# control_03_12_2018.net
KiCad netlist of a schematic drawn in EAGLE
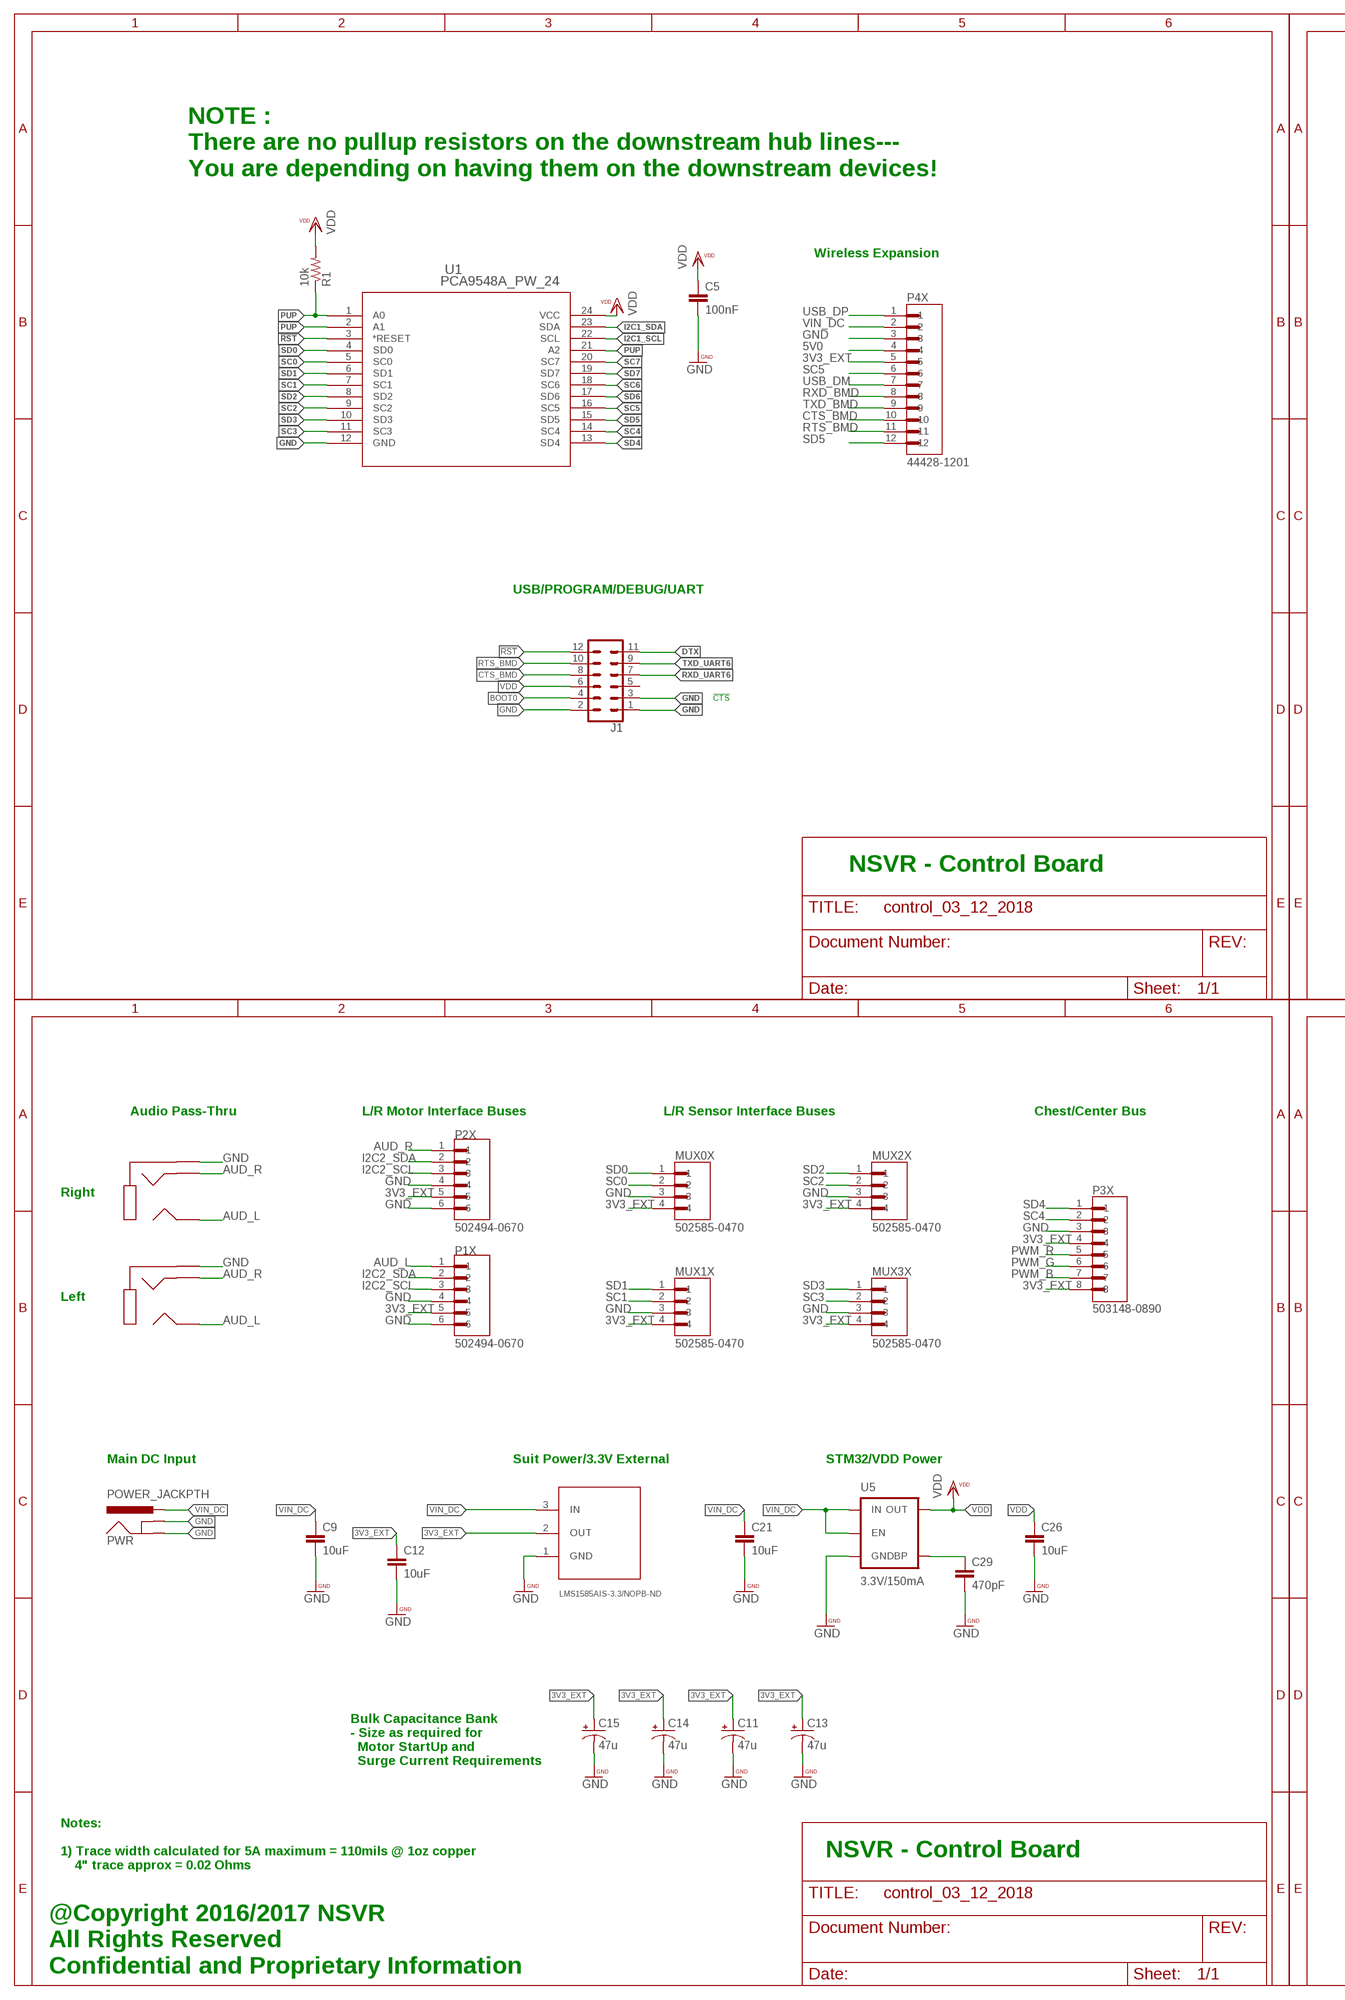
[diagram p0: schematic, sheet 1, part 1 of 2]
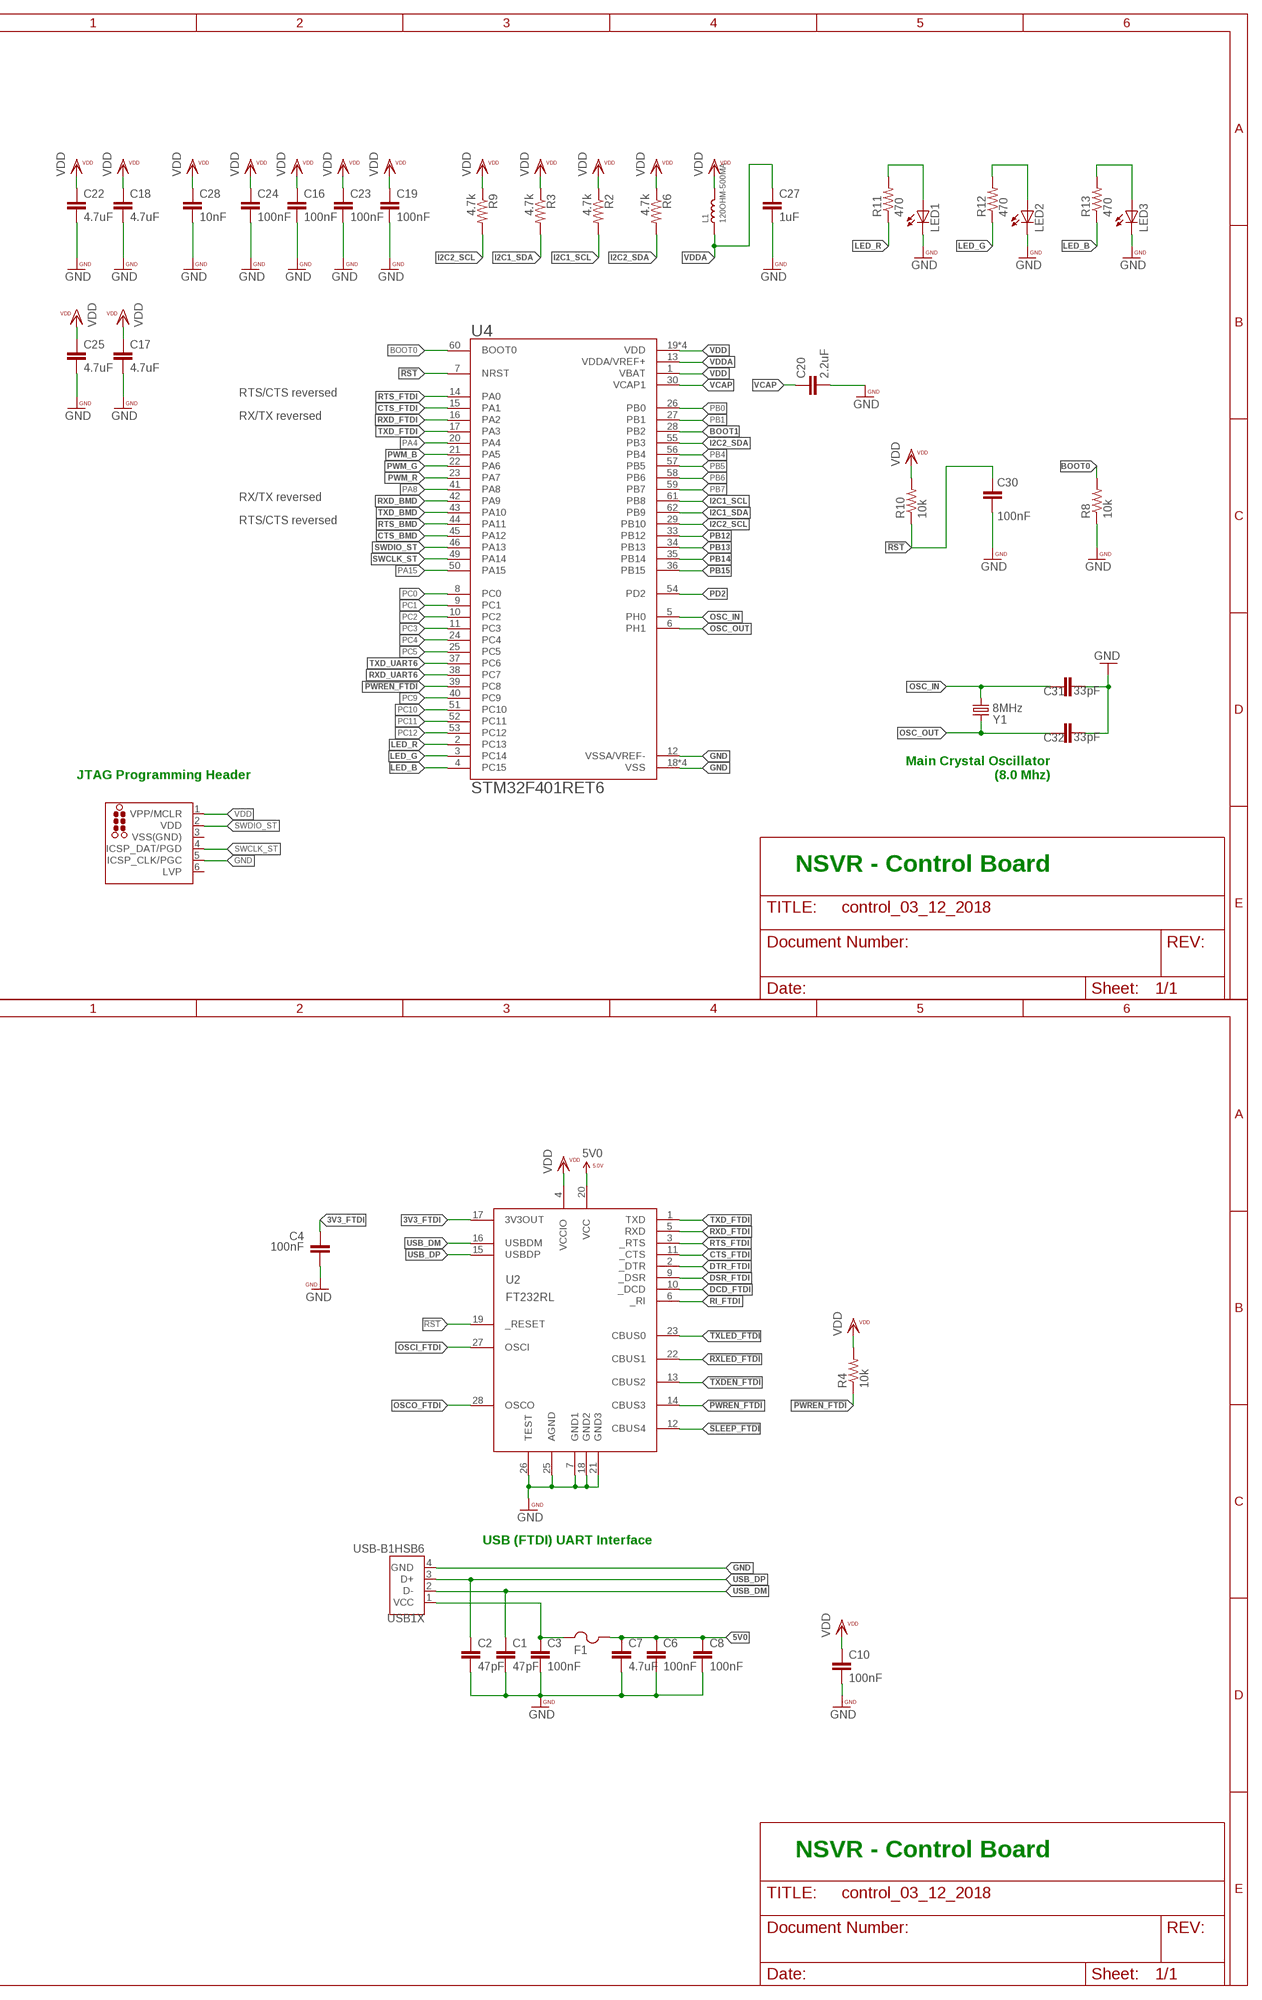
[diagram p1: schematic, sheet 1, part 2 of 2]

(export (version "E")
  (design (tool "Eeschema 10.0.6"))
  (components
    (comp (ref "C1")
      (value "47pF")
      (footprint "eagle-import:0402-CAP")
      (libsource (lib "eagle-import") (part "CAP0402-CAP"))
    )
    (comp (ref "C2")
      (value "47pF")
      (footprint "eagle-import:0402-CAP")
      (libsource (lib "eagle-import") (part "CAP0402-CAP"))
    )
    (comp (ref "C3")
      (value "100nF")
      (footprint "eagle-import:0402-CAP")
      (libsource (lib "eagle-import") (part "CAP0402-CAP"))
    )
    (comp (ref "C4")
      (value "100nF")
      (footprint "eagle-import:0402-CAP")
      (libsource (lib "eagle-import") (part "CAP0402-CAP"))
    )
    (comp (ref "C5")
      (value "100nF")
      (footprint "eagle-import:0402-CAP")
      (libsource (lib "eagle-import") (part "CAP0402-CAP"))
    )
    (comp (ref "C6")
      (value "100nF")
      (footprint "eagle-import:0402-CAP")
      (libsource (lib "eagle-import") (part "CAP0402-CAP"))
    )
    (comp (ref "C7")
      (value "4.7uF")
      (footprint "eagle-import:0402-CAP")
      (libsource (lib "eagle-import") (part "CAP0402-CAP"))
    )
    (comp (ref "C8")
      (value "100nF")
      (footprint "eagle-import:0402-CAP")
      (libsource (lib "eagle-import") (part "CAP0402-CAP"))
    )
    (comp (ref "C9")
      (value "10uF")
      (footprint "eagle-import:0603-CAP")
      (libsource (lib "eagle-import") (part "CAP0603-CAP"))
    )
    (comp (ref "C10")
      (value "100nF")
      (footprint "eagle-import:0402-CAP")
      (libsource (lib "eagle-import") (part "CAP0402-CAP"))
    )
    (comp (ref "C11")
      (value "47u")
      (footprint "eagle-import:PANASONIC_D")
      (libsource (lib "eagle-import") (part "CAP_POLD"))
    )
    (comp (ref "C12")
      (value "10uF")
      (footprint "eagle-import:0603-CAP")
      (libsource (lib "eagle-import") (part "CAP0603-CAP"))
    )
    (comp (ref "C13")
      (value "47u")
      (footprint "eagle-import:PANASONIC_D")
      (libsource (lib "eagle-import") (part "CAP_POLD"))
    )
    (comp (ref "C14")
      (value "47u")
      (footprint "eagle-import:PANASONIC_D")
      (libsource (lib "eagle-import") (part "CAP_POLD"))
    )
    (comp (ref "C15")
      (value "47u")
      (footprint "eagle-import:PANASONIC_D")
      (libsource (lib "eagle-import") (part "CAP_POLD"))
    )
    (comp (ref "C16")
      (value "100nF")
      (footprint "eagle-import:0402-CAP")
      (libsource (lib "eagle-import") (part "CAP0402-CAP"))
    )
    (comp (ref "C17")
      (value "4.7uF")
      (footprint "eagle-import:0402-CAP")
      (libsource (lib "eagle-import") (part "CAP0402-CAP"))
    )
    (comp (ref "C18")
      (value "4.7uF")
      (footprint "eagle-import:0402-CAP")
      (libsource (lib "eagle-import") (part "CAP0402-CAP"))
    )
    (comp (ref "C19")
      (value "100nF")
      (footprint "eagle-import:0402-CAP")
      (libsource (lib "eagle-import") (part "CAP0402-CAP"))
    )
    (comp (ref "C20")
      (value "2.2uF")
      (footprint "eagle-import:0402-CAP")
      (libsource (lib "eagle-import") (part "CAP0402-CAP"))
    )
    (comp (ref "C21")
      (value "10uF")
      (footprint "eagle-import:0603-CAP")
      (libsource (lib "eagle-import") (part "CAP0603-CAP"))
    )
    (comp (ref "C22")
      (value "4.7uF")
      (footprint "eagle-import:0402-CAP")
      (libsource (lib "eagle-import") (part "CAP0402-CAP"))
    )
    (comp (ref "C23")
      (value "100nF")
      (footprint "eagle-import:0402-CAP")
      (libsource (lib "eagle-import") (part "CAP0402-CAP"))
    )
    (comp (ref "C24")
      (value "100nF")
      (footprint "eagle-import:0402-CAP")
      (libsource (lib "eagle-import") (part "CAP0402-CAP"))
    )
    (comp (ref "C25")
      (value "4.7uF")
      (footprint "eagle-import:0402-CAP")
      (libsource (lib "eagle-import") (part "CAP0402-CAP"))
    )
    (comp (ref "C26")
      (value "10uF")
      (footprint "eagle-import:0603-CAP")
      (libsource (lib "eagle-import") (part "CAP0603-CAP"))
    )
    (comp (ref "C27")
      (value "1uF")
      (footprint "eagle-import:0402-CAP")
      (libsource (lib "eagle-import") (part "CAP0402-CAP"))
    )
    (comp (ref "C28")
      (value "10nF")
      (footprint "eagle-import:0402-CAP")
      (libsource (lib "eagle-import") (part "CAP0402-CAP"))
    )
    (comp (ref "C29")
      (value "470pF")
      (footprint "eagle-import:0402-CAP")
      (libsource (lib "eagle-import") (part "CAP0402-CAP"))
    )
    (comp (ref "C30")
      (value "100nF")
      (footprint "eagle-import:0402-CAP")
      (libsource (lib "eagle-import") (part "CAP0402-CAP"))
    )
    (comp (ref "C31")
      (value "33pF")
      (footprint "eagle-import:0402-CAP")
      (libsource (lib "eagle-import") (part "CAP0402-CAP"))
    )
    (comp (ref "C32")
      (value "33pF")
      (footprint "eagle-import:0402-CAP")
      (libsource (lib "eagle-import") (part "CAP0402-CAP"))
    )
    (comp (ref "F1")
      (value "1206L050YR")
      (footprint "eagle-import:1206LSERIES")
      (fields (field (name "COPYRIGHT") "Copyright C 2015 Accelerated Designs. All rights reserved"))
      (libsource (lib "eagle-import") (part "1206L050YR"))
    )
    (comp (ref "J1")
      (value "CONN_06X2SMD_FEMALE")
      (footprint "eagle-import:2X6_SMD")
      (libsource (lib "eagle-import") (part "CONN_06X2SMD_FEMALE"))
    )
    (comp (ref "J_ST")
      (value "TC2030-MCP-NL")
      (footprint "eagle-import:TC2030-MCP-NL")
      (libsource (lib "eagle-import") (part "TC2030-MCP-NL"))
    )
    (comp (ref "L1")
      (value "120OHM-500MA")
      (footprint "eagle-import:L0603")
      (fields (field (name "MPN") "BLM18AG121SN1D"))
      (libsource (lib "eagle-import") (part "SMD-FERRITE-CHIP-120-OHM-500MA(0603)"))
    )
    (comp (ref "LED1")
      (value "LEDCHIP-LED0603")
      (footprint "eagle-import:CHIP-LED0603")
      (libsource (lib "eagle-import") (part "LEDCHIP-LED0603"))
    )
    (comp (ref "LED2")
      (value "LEDCHIP-LED0603")
      (footprint "eagle-import:CHIP-LED0603")
      (libsource (lib "eagle-import") (part "LEDCHIP-LED0603"))
    )
    (comp (ref "LED3")
      (value "LEDCHIP-LED0603")
      (footprint "eagle-import:CHIP-LED0603")
      (libsource (lib "eagle-import") (part "LEDCHIP-LED0603"))
    )
    (comp (ref "MUX0X")
      (value "502585-0470")
      (footprint "eagle-import:MOLEX_502585-0470")
      (fields (field (name "MF") "Molex"))
      (libsource (lib "eagle-import") (part "502585-0470"))
    )
    (comp (ref "MUX1X")
      (value "502585-0470")
      (footprint "eagle-import:MOLEX_502585-0470")
      (fields (field (name "MF") "Molex"))
      (libsource (lib "eagle-import") (part "502585-0470"))
    )
    (comp (ref "MUX2X")
      (value "502585-0470")
      (footprint "eagle-import:MOLEX_502585-0470")
      (fields (field (name "MF") "Molex"))
      (libsource (lib "eagle-import") (part "502585-0470"))
    )
    (comp (ref "MUX3X")
      (value "502585-0470")
      (footprint "eagle-import:MOLEX_502585-0470")
      (fields (field (name "MF") "Molex"))
      (libsource (lib "eagle-import") (part "502585-0470"))
    )
    (comp (ref "P1X")
      (value "502494-0670")
      (footprint "eagle-import:MOLEX_502494-0670")
      (fields (field (name "MF") "Molex"))
      (libsource (lib "eagle-import") (part "502494-0670"))
    )
    (comp (ref "P2X")
      (value "502494-0670")
      (footprint "eagle-import:MOLEX_502494-0670")
      (fields (field (name "MF") "Molex"))
      (libsource (lib "eagle-import") (part "502494-0670"))
    )
    (comp (ref "P3X")
      (value "503148-0890")
      (footprint "eagle-import:MOLEX_503148-0890")
      (fields (field (name "MF") "Molex"))
      (libsource (lib "eagle-import") (part "503148-0890"))
    )
    (comp (ref "P4X")
      (value "44428-1201")
      (footprint "eagle-import:MOLEX_44428-1201")
      (fields (field (name "MF") "Molex"))
      (libsource (lib "eagle-import") (part "44428-1201"))
    )
    (comp (ref "PJ1")
      (value "SJ1-3513N")
      (footprint "eagle-import:SJ1-351XN")
      (libsource (lib "eagle-import") (part "SJ1-3513N"))
    )
    (comp (ref "PJ2")
      (value "SJ1-3513N")
      (footprint "eagle-import:SJ1-351XN")
      (libsource (lib "eagle-import") (part "SJ1-3513N"))
    )
    (comp (ref "PWR")
      (value "POWER_JACKPTH")
      (footprint "eagle-import:POWER_JACK_PTH")
      (libsource (lib "eagle-import") (part "POWER_JACKPTH"))
    )
    (comp (ref "R1")
      (value "10k")
      (footprint "eagle-import:EIA-0402")
      (libsource (lib "eagle-import") (part "RESISTOR0402-TYP"))
    )
    (comp (ref "R2")
      (value "4.7k")
      (footprint "eagle-import:EIA-0402")
      (libsource (lib "eagle-import") (part "RESISTOR0402-TYP"))
    )
    (comp (ref "R3")
      (value "4.7k")
      (footprint "eagle-import:EIA-0402")
      (libsource (lib "eagle-import") (part "RESISTOR0402-TYP"))
    )
    (comp (ref "R4")
      (value "10k")
      (footprint "eagle-import:EIA-0402")
      (libsource (lib "eagle-import") (part "RESISTOR0402-TYP"))
    )
    (comp (ref "R6")
      (value "4.7k")
      (footprint "eagle-import:EIA-0402")
      (libsource (lib "eagle-import") (part "RESISTOR0402-TYP"))
    )
    (comp (ref "R8")
      (value "10k")
      (footprint "eagle-import:EIA-0402")
      (libsource (lib "eagle-import") (part "RESISTOR0402-TYP"))
    )
    (comp (ref "R9")
      (value "4.7k")
      (footprint "eagle-import:EIA-0402")
      (libsource (lib "eagle-import") (part "RESISTOR0402-TYP"))
    )
    (comp (ref "R10")
      (value "10k")
      (footprint "eagle-import:EIA-0402")
      (libsource (lib "eagle-import") (part "RESISTOR0402-TYP"))
    )
    (comp (ref "R11")
      (value "470")
      (footprint "eagle-import:EIA-0402")
      (libsource (lib "eagle-import") (part "RESISTOR0402-TYP"))
    )
    (comp (ref "R12")
      (value "470")
      (footprint "eagle-import:EIA-0402")
      (libsource (lib "eagle-import") (part "RESISTOR0402-TYP"))
    )
    (comp (ref "R13")
      (value "470")
      (footprint "eagle-import:EIA-0402")
      (libsource (lib "eagle-import") (part "RESISTOR0402-TYP"))
    )
    (comp (ref "U1")
      (value "PCA9548A_PW_24")
      (footprint "eagle-import:PW24")
      (fields
        (field (name "GENERIC_PART_NUMBER") "PCA9548A")
        (field (name "MANUFACTURER") "Texas Instruments")
        (field (name "MANUFACTURER_PART_NUMBER") "pca9548a_pw_24")
      )
      (libsource (lib "eagle-import") (part "PCA9548A_PW_24"))
    )
    (comp (ref "U2")
      (value "FT232RL")
      (footprint "eagle-import:SSOP28DB")
      (libsource (lib "eagle-import") (part "FT232RL"))
    )
    (comp (ref "U3")
      (value "LMS1585AIS-3.3/NOPB-ND")
      (footprint "eagle-import:TO254P1524X483-4N")
      (libsource (lib "eagle-import") (part "LMS1585AIS-3.3/NOPB-ND"))
    )
    (comp (ref "U4")
      (value "STM32F401RET6")
      (footprint "eagle-import:QFP50P1200X1200X160-64N")
      (fields (field (name "MF") "STMicroelectronics"))
      (libsource (lib "eagle-import") (part "STM32F401RET6"))
    )
    (comp (ref "U5")
      (value "3.3V/150mA")
      (footprint "eagle-import:SOT23-5")
      (libsource (lib "eagle-import") (part "V_REG_MIC52053.3V"))
    )
    (comp (ref "USB1X")
      (value "USB-B1HSB6")
      (footprint "eagle-import:OST_USB-B1HSB6")
      (fields (field (name "MF") "On Shore Technology"))
      (libsource (lib "eagle-import") (part "USB-B1HSB6"))
    )
    (comp (ref "Y1")
      (value "8MHz")
      (footprint "eagle-import:CRYSTAL-SMD-5X3")
      (libsource (lib "eagle-import") (part "CRYSTAL5X3"))
    )
  )
  (nets
    (net (code "1") (name "/AUD_L") (class "Default")
      (node (ref "P1X") (pin "1") (pinfunction "1_1") (pintype "passive"))
      (node (ref "PJ1") (pin "2") (pinfunction "2_2") (pintype "bidirectional"))
      (node (ref "PJ2") (pin "2") (pinfunction "2_2") (pintype "bidirectional"))
    )
    (net (code "2") (name "/AUD_R") (class "Default")
      (node (ref "P2X") (pin "1") (pinfunction "1_1") (pintype "passive"))
      (node (ref "PJ1") (pin "3") (pinfunction "3_3") (pintype "bidirectional"))
      (node (ref "PJ2") (pin "3") (pinfunction "3_3") (pintype "bidirectional"))
    )
    (net (code "3") (name "/VSS(GND)") (class "Default")
      (node (ref "J_ST") (pin "3") (pinfunction "VSS(GND)_3") (pintype "power_in"))
    )
    (net (code "4") (name "/~{PWREN_FTDI}") (class "Default")
      (node (ref "R4") (pin "1") (pinfunction "1_1") (pintype "passive"))
      (node (ref "U2") (pin "14") (pinfunction "CBUS3_14") (pintype "bidirectional"))
      (node (ref "U4") (pin "39") (pinfunction "PC8_39") (pintype "bidirectional"))
    )
    (net (code "5") (name "/~{RST}") (class "Default")
      (node (ref "C30") (pin "1") (pinfunction "1_1") (pintype "passive"))
      (node (ref "J1") (pin "12") (pinfunction "12_12") (pintype "passive"))
      (node (ref "R10") (pin "1") (pinfunction "1_1") (pintype "passive"))
      (node (ref "U1") (pin "3") (pinfunction "*RESET_3") (pintype "input"))
      (node (ref "U2") (pin "19") (pinfunction "_RESET_19") (pintype "input"))
      (node (ref "U4") (pin "7") (pinfunction "NRST_7") (pintype "bidirectional"))
    )
    (net (code "6") (name "/~{RXLED_FTDI}") (class "Default")
      (node (ref "U2") (pin "22") (pinfunction "CBUS1_22") (pintype "bidirectional"))
    )
    (net (code "7") (name "/~{SLEEP_FTDI}") (class "Default")
      (node (ref "U2") (pin "12") (pinfunction "CBUS4_12") (pintype "bidirectional"))
    )
    (net (code "8") (name "/~{TXDEN_FTDI}") (class "Default")
      (node (ref "U2") (pin "13") (pinfunction "CBUS2_13") (pintype "bidirectional"))
    )
    (net (code "9") (name "/~{TXLED_FTDI}") (class "Default")
      (node (ref "U2") (pin "23") (pinfunction "CBUS0_23") (pintype "bidirectional"))
    )
    (net (code "10") (name "3V3_EXT") (class "Default")
      (node (ref "C11") (pin "+") (pinfunction "+_+") (pintype "passive"))
      (node (ref "C12") (pin "1") (pinfunction "1_1") (pintype "passive"))
      (node (ref "C13") (pin "+") (pinfunction "+_+") (pintype "passive"))
      (node (ref "C14") (pin "+") (pinfunction "+_+") (pintype "passive"))
      (node (ref "C15") (pin "+") (pinfunction "+_+") (pintype "passive"))
      (node (ref "MUX0X") (pin "4") (pinfunction "4_4") (pintype "passive"))
      (node (ref "MUX1X") (pin "4") (pinfunction "4_4") (pintype "passive"))
      (node (ref "MUX2X") (pin "4") (pinfunction "4_4") (pintype "passive"))
      (node (ref "MUX3X") (pin "4") (pinfunction "4_4") (pintype "passive"))
      (node (ref "P1X") (pin "5") (pinfunction "5_5") (pintype "passive"))
      (node (ref "P2X") (pin "5") (pinfunction "5_5") (pintype "passive"))
      (node (ref "P3X") (pin "4") (pinfunction "4_4") (pintype "passive"))
      (node (ref "P3X") (pin "8") (pinfunction "8_8") (pintype "passive"))
      (node (ref "P4X") (pin "5") (pinfunction "5_5") (pintype "passive"))
      (node (ref "U3") (pin "2") (pinfunction "OUT_2") (pintype "bidirectional"))
    )
    (net (code "11") (name "3V3_FTDI") (class "Default")
      (node (ref "C4") (pin "1") (pinfunction "1_1") (pintype "passive"))
      (node (ref "U2") (pin "17") (pinfunction "3V3OUT_17") (pintype "output"))
    )
    (net (code "12") (name "5V0") (class "Default")
      (node (ref "C6") (pin "1") (pinfunction "1_1") (pintype "passive"))
      (node (ref "C7") (pin "1") (pinfunction "1_1") (pintype "passive"))
      (node (ref "C8") (pin "1") (pinfunction "1_1") (pintype "passive"))
      (node (ref "F1") (pin "2") (pinfunction "2_2") (pintype "passive"))
      (node (ref "P4X") (pin "4") (pinfunction "4_4") (pintype "passive"))
      (node (ref "U2") (pin "20") (pinfunction "VCC_20") (pintype "power_in"))
    )
    (net (code "13") (name "BOOT0") (class "Default")
      (node (ref "J1") (pin "4") (pinfunction "4_4") (pintype "passive"))
      (node (ref "R8") (pin "2") (pinfunction "2_2") (pintype "passive"))
      (node (ref "U4") (pin "60") (pinfunction "BOOT0_60") (pintype "input"))
    )
    (net (code "14") (name "BOOT1") (class "Default")
      (node (ref "U4") (pin "28") (pinfunction "PB2_28") (pintype "bidirectional"))
    )
    (net (code "15") (name "CTS_BMD") (class "Default")
      (node (ref "J1") (pin "8") (pinfunction "8_8") (pintype "passive"))
      (node (ref "P4X") (pin "10") (pinfunction "10_10") (pintype "passive"))
      (node (ref "U4") (pin "45") (pinfunction "PA12_45") (pintype "bidirectional"))
    )
    (net (code "16") (name "CTS_FTDI") (class "Default")
      (node (ref "U2") (pin "11") (pinfunction "_CTS_11") (pintype "input"))
      (node (ref "U4") (pin "15") (pinfunction "PA1_15") (pintype "bidirectional"))
    )
    (net (code "17") (name "DCD_FTDI") (class "Default")
      (node (ref "U2") (pin "10") (pinfunction "_DCD_10") (pintype "input"))
    )
    (net (code "18") (name "DSR_FTDI") (class "Default")
      (node (ref "U2") (pin "9") (pinfunction "_DSR_9") (pintype "input"))
    )
    (net (code "19") (name "DTR_FTDI") (class "Default")
      (node (ref "U2") (pin "2") (pinfunction "_DTR_2") (pintype "output"))
    )
    (net (code "20") (name "DTX") (class "Default")
      (node (ref "J1") (pin "11") (pinfunction "11_11") (pintype "passive"))
    )
    (net (code "21") (name "GND") (class "Default")
      (node (ref "C1") (pin "2") (pinfunction "2_2") (pintype "passive"))
      (node (ref "C10") (pin "2") (pinfunction "2_2") (pintype "passive"))
      (node (ref "C11") (pin "-") (pinfunction "-_-") (pintype "passive"))
      (node (ref "C12") (pin "2") (pinfunction "2_2") (pintype "passive"))
      (node (ref "C13") (pin "-") (pinfunction "-_-") (pintype "passive"))
      (node (ref "C14") (pin "-") (pinfunction "-_-") (pintype "passive"))
      (node (ref "C15") (pin "-") (pinfunction "-_-") (pintype "passive"))
      (node (ref "C16") (pin "2") (pinfunction "2_2") (pintype "passive"))
      (node (ref "C17") (pin "2") (pinfunction "2_2") (pintype "passive"))
      (node (ref "C18") (pin "2") (pinfunction "2_2") (pintype "passive"))
      (node (ref "C19") (pin "2") (pinfunction "2_2") (pintype "passive"))
      (node (ref "C2") (pin "2") (pinfunction "2_2") (pintype "passive"))
      (node (ref "C20") (pin "2") (pinfunction "2_2") (pintype "passive"))
      (node (ref "C21") (pin "2") (pinfunction "2_2") (pintype "passive"))
      (node (ref "C22") (pin "2") (pinfunction "2_2") (pintype "passive"))
      (node (ref "C23") (pin "2") (pinfunction "2_2") (pintype "passive"))
      (node (ref "C24") (pin "2") (pinfunction "2_2") (pintype "passive"))
      (node (ref "C25") (pin "2") (pinfunction "2_2") (pintype "passive"))
      (node (ref "C26") (pin "2") (pinfunction "2_2") (pintype "passive"))
      (node (ref "C27") (pin "2") (pinfunction "2_2") (pintype "passive"))
      (node (ref "C28") (pin "2") (pinfunction "2_2") (pintype "passive"))
      (node (ref "C29") (pin "2") (pinfunction "2_2") (pintype "passive"))
      (node (ref "C3") (pin "2") (pinfunction "2_2") (pintype "passive"))
      (node (ref "C30") (pin "2") (pinfunction "2_2") (pintype "passive"))
      (node (ref "C31") (pin "1") (pinfunction "1_1") (pintype "passive"))
      (node (ref "C32") (pin "1") (pinfunction "1_1") (pintype "passive"))
      (node (ref "C4") (pin "2") (pinfunction "2_2") (pintype "passive"))
      (node (ref "C5") (pin "2") (pinfunction "2_2") (pintype "passive"))
      (node (ref "C6") (pin "2") (pinfunction "2_2") (pintype "passive"))
      (node (ref "C7") (pin "2") (pinfunction "2_2") (pintype "passive"))
      (node (ref "C8") (pin "2") (pinfunction "2_2") (pintype "passive"))
      (node (ref "C9") (pin "2") (pinfunction "2_2") (pintype "passive"))
      (node (ref "J1") (pin "1") (pinfunction "1_1") (pintype "passive"))
      (node (ref "J1") (pin "2") (pinfunction "2_2") (pintype "passive"))
      (node (ref "J1") (pin "3") (pinfunction "3_3") (pintype "passive"))
      (node (ref "J_ST") (pin "5") (pinfunction "ICSP_CLK/PGC_5") (pintype "output"))
      (node (ref "LED1") (pin "C") (pinfunction "C_C") (pintype "passive"))
      (node (ref "LED2") (pin "C") (pinfunction "C_C") (pintype "passive"))
      (node (ref "LED3") (pin "C") (pinfunction "C_C") (pintype "passive"))
      (node (ref "MUX0X") (pin "3") (pinfunction "3_3") (pintype "passive"))
      (node (ref "MUX1X") (pin "3") (pinfunction "3_3") (pintype "passive"))
      (node (ref "MUX2X") (pin "3") (pinfunction "3_3") (pintype "passive"))
      (node (ref "MUX3X") (pin "3") (pinfunction "3_3") (pintype "passive"))
      (node (ref "P1X") (pin "4") (pinfunction "4_4") (pintype "passive"))
      (node (ref "P1X") (pin "6") (pinfunction "6_6") (pintype "passive"))
      (node (ref "P2X") (pin "4") (pinfunction "4_4") (pintype "passive"))
      (node (ref "P2X") (pin "6") (pinfunction "6_6") (pintype "passive"))
      (node (ref "P3X") (pin "3") (pinfunction "3_3") (pintype "passive"))
      (node (ref "P4X") (pin "3") (pinfunction "3_3") (pintype "passive"))
      (node (ref "PJ1") (pin "1") (pinfunction "1_1") (pintype "bidirectional"))
      (node (ref "PJ2") (pin "1") (pinfunction "1_1") (pintype "bidirectional"))
      (node (ref "PWR") (pin "GND") (pinfunction "GND_GND") (pintype "bidirectional"))
      (node (ref "PWR") (pin "GNDBREAK") (pinfunction "GNDBREAK_GNDBREAK") (pintype "bidirectional"))
      (node (ref "R8") (pin "1") (pinfunction "1_1") (pintype "passive"))
      (node (ref "U1") (pin "12") (pinfunction "GND_12") (pintype "power_in"))
      (node (ref "U2") (pin "18") (pinfunction "GND2_18") (pintype "power_in"))
      (node (ref "U2") (pin "21") (pinfunction "GND3_21") (pintype "power_in"))
      (node (ref "U2") (pin "25") (pinfunction "AGND_25") (pintype "power_in"))
      (node (ref "U2") (pin "26") (pinfunction "TEST_26") (pintype "input"))
      (node (ref "U2") (pin "7") (pinfunction "GND1_7") (pintype "power_in"))
      (node (ref "U3") (pin "1") (pinfunction "GND_1") (pintype "bidirectional"))
      (node (ref "U4") (pin "12") (pinfunction "VSSA/VREF-_12") (pintype "power_in"))
      (node (ref "U4") (pin "18") (pinfunction "VSS_18") (pintype "power_in"))
      (node (ref "U4") (pin "31") (pinfunction "VSS_31") (pintype "power_in"))
      (node (ref "U4") (pin "47") (pinfunction "VSS_47") (pintype "power_in"))
      (node (ref "U4") (pin "63") (pinfunction "VSS_63") (pintype "power_in"))
      (node (ref "U5") (pin "2") (pinfunction "GND_2") (pintype "input"))
      (node (ref "USB1X") (pin "4") (pinfunction "GND_4") (pintype "power_in"))
    )
    (net (code "22") (name "I2C1_SCL") (class "Default")
      (node (ref "R2") (pin "2") (pinfunction "2_2") (pintype "passive"))
      (node (ref "U1") (pin "22") (pinfunction "SCL_22") (pintype "passive"))
      (node (ref "U4") (pin "61") (pinfunction "PB8_61") (pintype "bidirectional"))
    )
    (net (code "23") (name "I2C1_SDA") (class "Default")
      (node (ref "R3") (pin "2") (pinfunction "2_2") (pintype "passive"))
      (node (ref "U1") (pin "23") (pinfunction "SDA_23") (pintype "passive"))
      (node (ref "U4") (pin "62") (pinfunction "PB9_62") (pintype "bidirectional"))
    )
    (net (code "24") (name "I2C2_SCL") (class "Default")
      (node (ref "P1X") (pin "3") (pinfunction "3_3") (pintype "passive"))
      (node (ref "P2X") (pin "3") (pinfunction "3_3") (pintype "passive"))
      (node (ref "R9") (pin "2") (pinfunction "2_2") (pintype "passive"))
      (node (ref "U4") (pin "29") (pinfunction "PB10_29") (pintype "bidirectional"))
    )
    (net (code "25") (name "I2C2_SDA") (class "Default")
      (node (ref "P1X") (pin "2") (pinfunction "2_2") (pintype "passive"))
      (node (ref "P2X") (pin "2") (pinfunction "2_2") (pintype "passive"))
      (node (ref "R6") (pin "2") (pinfunction "2_2") (pintype "passive"))
      (node (ref "U4") (pin "55") (pinfunction "PB3_55") (pintype "bidirectional"))
    )
    (net (code "26") (name "LED_B") (class "Default")
      (node (ref "R13") (pin "1") (pinfunction "1_1") (pintype "passive"))
      (node (ref "U4") (pin "4") (pinfunction "PC15_4") (pintype "bidirectional"))
    )
    (net (code "27") (name "LED_G") (class "Default")
      (node (ref "R12") (pin "1") (pinfunction "1_1") (pintype "passive"))
      (node (ref "U4") (pin "3") (pinfunction "PC14_3") (pintype "bidirectional"))
    )
    (net (code "28") (name "LED_R") (class "Default")
      (node (ref "R11") (pin "1") (pinfunction "1_1") (pintype "passive"))
      (node (ref "U4") (pin "2") (pinfunction "PC13_2") (pintype "bidirectional"))
    )
    (net (code "29") (name "Net-(LED1-PadA)") (class "Default")
      (node (ref "LED1") (pin "A") (pinfunction "A_A") (pintype "passive"))
      (node (ref "R11") (pin "2") (pinfunction "2_2") (pintype "passive"))
    )
    (net (code "30") (name "Net-(LED2-PadA)") (class "Default")
      (node (ref "LED2") (pin "A") (pinfunction "A_A") (pintype "passive"))
      (node (ref "R12") (pin "2") (pinfunction "2_2") (pintype "passive"))
    )
    (net (code "31") (name "Net-(LED3-PadA)") (class "Default")
      (node (ref "LED3") (pin "A") (pinfunction "A_A") (pintype "passive"))
      (node (ref "R13") (pin "2") (pinfunction "2_2") (pintype "passive"))
    )
    (net (code "32") (name "Net-(U5-BP)") (class "Default")
      (node (ref "C29") (pin "1") (pinfunction "1_1") (pintype "passive"))
      (node (ref "U5") (pin "4") (pinfunction "BP_4") (pintype "input"))
    )
    (net (code "33") (name "Net-(USB1X-VCC)") (class "Default")
      (node (ref "C3") (pin "1") (pinfunction "1_1") (pintype "passive"))
      (node (ref "F1") (pin "1") (pinfunction "1_1") (pintype "passive"))
      (node (ref "USB1X") (pin "1") (pinfunction "VCC_1") (pintype "power_in"))
    )
    (net (code "34") (name "OSCI_FTDI") (class "Default")
      (node (ref "U2") (pin "27") (pinfunction "OSCI_27") (pintype "input"))
    )
    (net (code "35") (name "OSCO_FTDI") (class "Default")
      (node (ref "U2") (pin "28") (pinfunction "OSCO_28") (pintype "output"))
    )
    (net (code "36") (name "OSC_IN") (class "Default")
      (node (ref "C31") (pin "2") (pinfunction "2_2") (pintype "passive"))
      (node (ref "U4") (pin "5") (pinfunction "PH0_5") (pintype "bidirectional"))
      (node (ref "Y1") (pin "1") (pinfunction "1_1") (pintype "passive"))
    )
    (net (code "37") (name "OSC_OUT") (class "Default")
      (node (ref "C32") (pin "2") (pinfunction "2_2") (pintype "passive"))
      (node (ref "U4") (pin "6") (pinfunction "PH1_6") (pintype "bidirectional"))
      (node (ref "Y1") (pin "3") (pinfunction "2_3") (pintype "passive"))
    )
    (net (code "38") (name "PA4") (class "Default")
      (node (ref "U4") (pin "20") (pinfunction "PA4_20") (pintype "bidirectional"))
    )
    (net (code "39") (name "PA8") (class "Default")
      (node (ref "U4") (pin "41") (pinfunction "PA8_41") (pintype "bidirectional"))
    )
    (net (code "40") (name "PA15") (class "Default")
      (node (ref "U4") (pin "50") (pinfunction "PA15_50") (pintype "bidirectional"))
    )
    (net (code "41") (name "PB0") (class "Default")
      (node (ref "U4") (pin "26") (pinfunction "PB0_26") (pintype "bidirectional"))
    )
    (net (code "42") (name "PB1") (class "Default")
      (node (ref "U4") (pin "27") (pinfunction "PB1_27") (pintype "bidirectional"))
    )
    (net (code "43") (name "PB4") (class "Default")
      (node (ref "U4") (pin "56") (pinfunction "PB4_56") (pintype "bidirectional"))
    )
    (net (code "44") (name "PB5") (class "Default")
      (node (ref "U4") (pin "57") (pinfunction "PB5_57") (pintype "bidirectional"))
    )
    (net (code "45") (name "PB6") (class "Default")
      (node (ref "U4") (pin "58") (pinfunction "PB6_58") (pintype "bidirectional"))
    )
    (net (code "46") (name "PB7") (class "Default")
      (node (ref "U4") (pin "59") (pinfunction "PB7_59") (pintype "bidirectional"))
    )
    (net (code "47") (name "PB12") (class "Default")
      (node (ref "U4") (pin "33") (pinfunction "PB12_33") (pintype "bidirectional"))
    )
    (net (code "48") (name "PB13") (class "Default")
      (node (ref "U4") (pin "34") (pinfunction "PB13_34") (pintype "bidirectional"))
    )
    (net (code "49") (name "PB14") (class "Default")
      (node (ref "U4") (pin "35") (pinfunction "PB14_35") (pintype "bidirectional"))
    )
    (net (code "50") (name "PB15") (class "Default")
      (node (ref "U4") (pin "36") (pinfunction "PB15_36") (pintype "bidirectional"))
    )
    (net (code "51") (name "PC0") (class "Default")
      (node (ref "U4") (pin "8") (pinfunction "PC0_8") (pintype "bidirectional"))
    )
    (net (code "52") (name "PC1") (class "Default")
      (node (ref "U4") (pin "9") (pinfunction "PC1_9") (pintype "bidirectional"))
    )
    (net (code "53") (name "PC2") (class "Default")
      (node (ref "U4") (pin "10") (pinfunction "PC2_10") (pintype "bidirectional"))
    )
    (net (code "54") (name "PC3") (class "Default")
      (node (ref "U4") (pin "11") (pinfunction "PC3_11") (pintype "bidirectional"))
    )
    (net (code "55") (name "PC4") (class "Default")
      (node (ref "U4") (pin "24") (pinfunction "PC4_24") (pintype "bidirectional"))
    )
    (net (code "56") (name "PC5") (class "Default")
      (node (ref "U4") (pin "25") (pinfunction "PC5_25") (pintype "bidirectional"))
    )
    (net (code "57") (name "PC9") (class "Default")
      (node (ref "U4") (pin "40") (pinfunction "PC9_40") (pintype "bidirectional"))
    )
    (net (code "58") (name "PC10") (class "Default")
      (node (ref "U4") (pin "51") (pinfunction "PC10_51") (pintype "bidirectional"))
    )
    (net (code "59") (name "PC11") (class "Default")
      (node (ref "U4") (pin "52") (pinfunction "PC11_52") (pintype "bidirectional"))
    )
    (net (code "60") (name "PC12") (class "Default")
      (node (ref "U4") (pin "53") (pinfunction "PC12_53") (pintype "bidirectional"))
    )
    (net (code "61") (name "PD2") (class "Default")
      (node (ref "U4") (pin "54") (pinfunction "PD2_54") (pintype "bidirectional"))
    )
    (net (code "62") (name "PUP") (class "Default")
      (node (ref "R1") (pin "1") (pinfunction "1_1") (pintype "passive"))
      (node (ref "U1") (pin "1") (pinfunction "A0_1") (pintype "input"))
      (node (ref "U1") (pin "2") (pinfunction "A1_2") (pintype "input"))
      (node (ref "U1") (pin "21") (pinfunction "A2_21") (pintype "input"))
    )
    (net (code "63") (name "PWM_B") (class "Default")
      (node (ref "P3X") (pin "7") (pinfunction "7_7") (pintype "passive"))
      (node (ref "U4") (pin "21") (pinfunction "PA5_21") (pintype "bidirectional"))
    )
    (net (code "64") (name "PWM_G") (class "Default")
      (node (ref "P3X") (pin "6") (pinfunction "6_6") (pintype "passive"))
      (node (ref "U4") (pin "22") (pinfunction "PA6_22") (pintype "bidirectional"))
    )
    (net (code "65") (name "PWM_R") (class "Default")
      (node (ref "P3X") (pin "5") (pinfunction "5_5") (pintype "passive"))
      (node (ref "U4") (pin "23") (pinfunction "PA7_23") (pintype "bidirectional"))
    )
    (net (code "66") (name "RI_FTDI") (class "Default")
      (node (ref "U2") (pin "6") (pinfunction "_RI_6") (pintype "input"))
    )
    (net (code "67") (name "RTS_BMD") (class "Default")
      (node (ref "J1") (pin "10") (pinfunction "10_10") (pintype "passive"))
      (node (ref "P4X") (pin "11") (pinfunction "11_11") (pintype "passive"))
      (node (ref "U4") (pin "44") (pinfunction "PA11_44") (pintype "bidirectional"))
    )
    (net (code "68") (name "RTS_FTDI") (class "Default")
      (node (ref "U2") (pin "3") (pinfunction "_RTS_3") (pintype "output"))
      (node (ref "U4") (pin "14") (pinfunction "PA0_14") (pintype "bidirectional"))
    )
    (net (code "69") (name "RXD_BMD") (class "Default")
      (node (ref "P4X") (pin "8") (pinfunction "8_8") (pintype "passive"))
      (node (ref "U4") (pin "42") (pinfunction "PA9_42") (pintype "bidirectional"))
    )
    (net (code "70") (name "RXD_FTDI") (class "Default")
      (node (ref "U2") (pin "5") (pinfunction "RXD_5") (pintype "input"))
      (node (ref "U4") (pin "16") (pinfunction "PA2_16") (pintype "bidirectional"))
    )
    (net (code "71") (name "RXD_UART6") (class "Default")
      (node (ref "J1") (pin "7") (pinfunction "7_7") (pintype "passive"))
      (node (ref "U4") (pin "38") (pinfunction "PC7_38") (pintype "bidirectional"))
    )
    (net (code "72") (name "SC0") (class "Default")
      (node (ref "MUX0X") (pin "2") (pinfunction "2_2") (pintype "passive"))
      (node (ref "U1") (pin "5") (pinfunction "SC0_5") (pintype "passive"))
    )
    (net (code "73") (name "SC1") (class "Default")
      (node (ref "MUX1X") (pin "2") (pinfunction "2_2") (pintype "passive"))
      (node (ref "U1") (pin "7") (pinfunction "SC1_7") (pintype "passive"))
    )
    (net (code "74") (name "SC2") (class "Default")
      (node (ref "MUX2X") (pin "2") (pinfunction "2_2") (pintype "passive"))
      (node (ref "U1") (pin "9") (pinfunction "SC2_9") (pintype "passive"))
    )
    (net (code "75") (name "SC3") (class "Default")
      (node (ref "MUX3X") (pin "2") (pinfunction "2_2") (pintype "passive"))
      (node (ref "U1") (pin "11") (pinfunction "SC3_11") (pintype "passive"))
    )
    (net (code "76") (name "SC4") (class "Default")
      (node (ref "P3X") (pin "2") (pinfunction "2_2") (pintype "passive"))
      (node (ref "U1") (pin "14") (pinfunction "SC4_14") (pintype "passive"))
    )
    (net (code "77") (name "SC5") (class "Default")
      (node (ref "P4X") (pin "6") (pinfunction "6_6") (pintype "passive"))
      (node (ref "U1") (pin "16") (pinfunction "SC5_16") (pintype "passive"))
    )
    (net (code "78") (name "SC6") (class "Default")
      (node (ref "U1") (pin "18") (pinfunction "SC6_18") (pintype "passive"))
    )
    (net (code "79") (name "SC7") (class "Default")
      (node (ref "U1") (pin "20") (pinfunction "SC7_20") (pintype "passive"))
    )
    (net (code "80") (name "SD0") (class "Default")
      (node (ref "MUX0X") (pin "1") (pinfunction "1_1") (pintype "passive"))
      (node (ref "U1") (pin "4") (pinfunction "SD0_4") (pintype "passive"))
    )
    (net (code "81") (name "SD1") (class "Default")
      (node (ref "MUX1X") (pin "1") (pinfunction "1_1") (pintype "passive"))
      (node (ref "U1") (pin "6") (pinfunction "SD1_6") (pintype "passive"))
    )
    (net (code "82") (name "SD2") (class "Default")
      (node (ref "MUX2X") (pin "1") (pinfunction "1_1") (pintype "passive"))
      (node (ref "U1") (pin "8") (pinfunction "SD2_8") (pintype "passive"))
    )
    (net (code "83") (name "SD3") (class "Default")
      (node (ref "MUX3X") (pin "1") (pinfunction "1_1") (pintype "passive"))
      (node (ref "U1") (pin "10") (pinfunction "SD3_10") (pintype "passive"))
    )
    (net (code "84") (name "SD4") (class "Default")
      (node (ref "P3X") (pin "1") (pinfunction "1_1") (pintype "passive"))
      (node (ref "U1") (pin "13") (pinfunction "SD4_13") (pintype "passive"))
    )
    (net (code "85") (name "SD5") (class "Default")
      (node (ref "P4X") (pin "12") (pinfunction "12_12") (pintype "passive"))
      (node (ref "U1") (pin "15") (pinfunction "SD5_15") (pintype "passive"))
    )
    (net (code "86") (name "SD6") (class "Default")
      (node (ref "U1") (pin "17") (pinfunction "SD6_17") (pintype "passive"))
    )
    (net (code "87") (name "SD7") (class "Default")
      (node (ref "U1") (pin "19") (pinfunction "SD7_19") (pintype "passive"))
    )
    (net (code "88") (name "SWCLK_ST") (class "Default")
      (node (ref "J_ST") (pin "4") (pinfunction "ICSP_DAT/PGD_4") (pintype "bidirectional"))
      (node (ref "U4") (pin "49") (pinfunction "PA14_49") (pintype "bidirectional"))
    )
    (net (code "89") (name "SWDIO_ST") (class "Default")
      (node (ref "J_ST") (pin "2") (pinfunction "VDD_2") (pintype "power_in"))
      (node (ref "U4") (pin "46") (pinfunction "PA13_46") (pintype "bidirectional"))
    )
    (net (code "90") (name "TXD_BMD") (class "Default")
      (node (ref "P4X") (pin "9") (pinfunction "9_9") (pintype "passive"))
      (node (ref "U4") (pin "43") (pinfunction "PA10_43") (pintype "bidirectional"))
    )
    (net (code "91") (name "TXD_FTDI") (class "Default")
      (node (ref "U2") (pin "1") (pinfunction "TXD_1") (pintype "output"))
      (node (ref "U4") (pin "17") (pinfunction "PA3_17") (pintype "bidirectional"))
    )
    (net (code "92") (name "TXD_UART6") (class "Default")
      (node (ref "J1") (pin "9") (pinfunction "9_9") (pintype "passive"))
      (node (ref "U4") (pin "37") (pinfunction "PC6_37") (pintype "bidirectional"))
    )
    (net (code "93") (name "USB_DM") (class "Default")
      (node (ref "C1") (pin "1") (pinfunction "1_1") (pintype "passive"))
      (node (ref "P4X") (pin "7") (pinfunction "7_7") (pintype "passive"))
      (node (ref "U2") (pin "16") (pinfunction "USBDM_16") (pintype "bidirectional"))
      (node (ref "USB1X") (pin "2") (pinfunction "D-_2") (pintype "bidirectional"))
    )
    (net (code "94") (name "USB_DP") (class "Default")
      (node (ref "C2") (pin "1") (pinfunction "1_1") (pintype "passive"))
      (node (ref "P4X") (pin "1") (pinfunction "1_1") (pintype "passive"))
      (node (ref "U2") (pin "15") (pinfunction "USBDP_15") (pintype "bidirectional"))
      (node (ref "USB1X") (pin "3") (pinfunction "D+_3") (pintype "bidirectional"))
    )
    (net (code "95") (name "VCAP") (class "Default")
      (node (ref "C20") (pin "1") (pinfunction "1_1") (pintype "passive"))
      (node (ref "U4") (pin "30") (pinfunction "VCAP1_30") (pintype "power_in"))
    )
    (net (code "96") (name "VDD") (class "Default")
      (node (ref "C10") (pin "1") (pinfunction "1_1") (pintype "passive"))
      (node (ref "C16") (pin "1") (pinfunction "1_1") (pintype "passive"))
      (node (ref "C17") (pin "1") (pinfunction "1_1") (pintype "passive"))
      (node (ref "C18") (pin "1") (pinfunction "1_1") (pintype "passive"))
      (node (ref "C19") (pin "1") (pinfunction "1_1") (pintype "passive"))
      (node (ref "C22") (pin "1") (pinfunction "1_1") (pintype "passive"))
      (node (ref "C23") (pin "1") (pinfunction "1_1") (pintype "passive"))
      (node (ref "C24") (pin "1") (pinfunction "1_1") (pintype "passive"))
      (node (ref "C25") (pin "1") (pinfunction "1_1") (pintype "passive"))
      (node (ref "C26") (pin "1") (pinfunction "1_1") (pintype "passive"))
      (node (ref "C28") (pin "1") (pinfunction "1_1") (pintype "passive"))
      (node (ref "C5") (pin "1") (pinfunction "1_1") (pintype "passive"))
      (node (ref "J1") (pin "6") (pinfunction "6_6") (pintype "passive"))
      (node (ref "J_ST") (pin "1") (pinfunction "VPP/MCLR_1") (pintype "passive"))
      (node (ref "L1") (pin "2") (pinfunction "2_2") (pintype "passive"))
      (node (ref "R1") (pin "2") (pinfunction "2_2") (pintype "passive"))
      (node (ref "R10") (pin "2") (pinfunction "2_2") (pintype "passive"))
      (node (ref "R2") (pin "1") (pinfunction "1_1") (pintype "passive"))
      (node (ref "R3") (pin "1") (pinfunction "1_1") (pintype "passive"))
      (node (ref "R4") (pin "2") (pinfunction "2_2") (pintype "passive"))
      (node (ref "R6") (pin "1") (pinfunction "1_1") (pintype "passive"))
      (node (ref "R9") (pin "1") (pinfunction "1_1") (pintype "passive"))
      (node (ref "U1") (pin "24") (pinfunction "VCC_24") (pintype "power_in"))
      (node (ref "U2") (pin "4") (pinfunction "VCCIO_4") (pintype "power_in"))
      (node (ref "U4") (pin "1") (pinfunction "VBAT_1") (pintype "power_in"))
      (node (ref "U4") (pin "19") (pinfunction "VDD_19") (pintype "power_in"))
      (node (ref "U4") (pin "32") (pinfunction "VDD_32") (pintype "power_in"))
      (node (ref "U4") (pin "48") (pinfunction "VDD_48") (pintype "power_in"))
      (node (ref "U4") (pin "64") (pinfunction "VDD_64") (pintype "power_in"))
      (node (ref "U5") (pin "5") (pinfunction "OUT_5") (pintype "passive"))
    )
    (net (code "97") (name "VDDA") (class "Default")
      (node (ref "C27") (pin "1") (pinfunction "1_1") (pintype "passive"))
      (node (ref "L1") (pin "1") (pinfunction "1_1") (pintype "passive"))
      (node (ref "U4") (pin "13") (pinfunction "VDDA/VREF+_13") (pintype "power_in"))
    )
    (net (code "98") (name "VIN_DC") (class "Default")
      (node (ref "C21") (pin "1") (pinfunction "1_1") (pintype "passive"))
      (node (ref "C9") (pin "1") (pinfunction "1_1") (pintype "passive"))
      (node (ref "P4X") (pin "2") (pinfunction "2_2") (pintype "passive"))
      (node (ref "PWR") (pin "PWR") (pinfunction "PWR_PWR") (pintype "bidirectional"))
      (node (ref "U3") (pin "3") (pinfunction "IN_3") (pintype "bidirectional"))
      (node (ref "U5") (pin "1") (pinfunction "IN_1") (pintype "input"))
      (node (ref "U5") (pin "3") (pinfunction "EN_3") (pintype "input"))
    )
    (net (code "99") (name "unconnected-(J1-Pad5)") (class "Default")
      (node (ref "J1") (pin "5") (pinfunction "5_5") (pintype "passive"))
    )
    (net (code "100") (name "unconnected-(J_ST-LVP-Pad6)") (class "Default")
      (node (ref "J_ST") (pin "6") (pinfunction "LVP_6") (pintype "bidirectional"))
    )
  )
)
